# SenseBox-Shield_v12.net
KiCad netlist of a schematic drawn in EAGLE
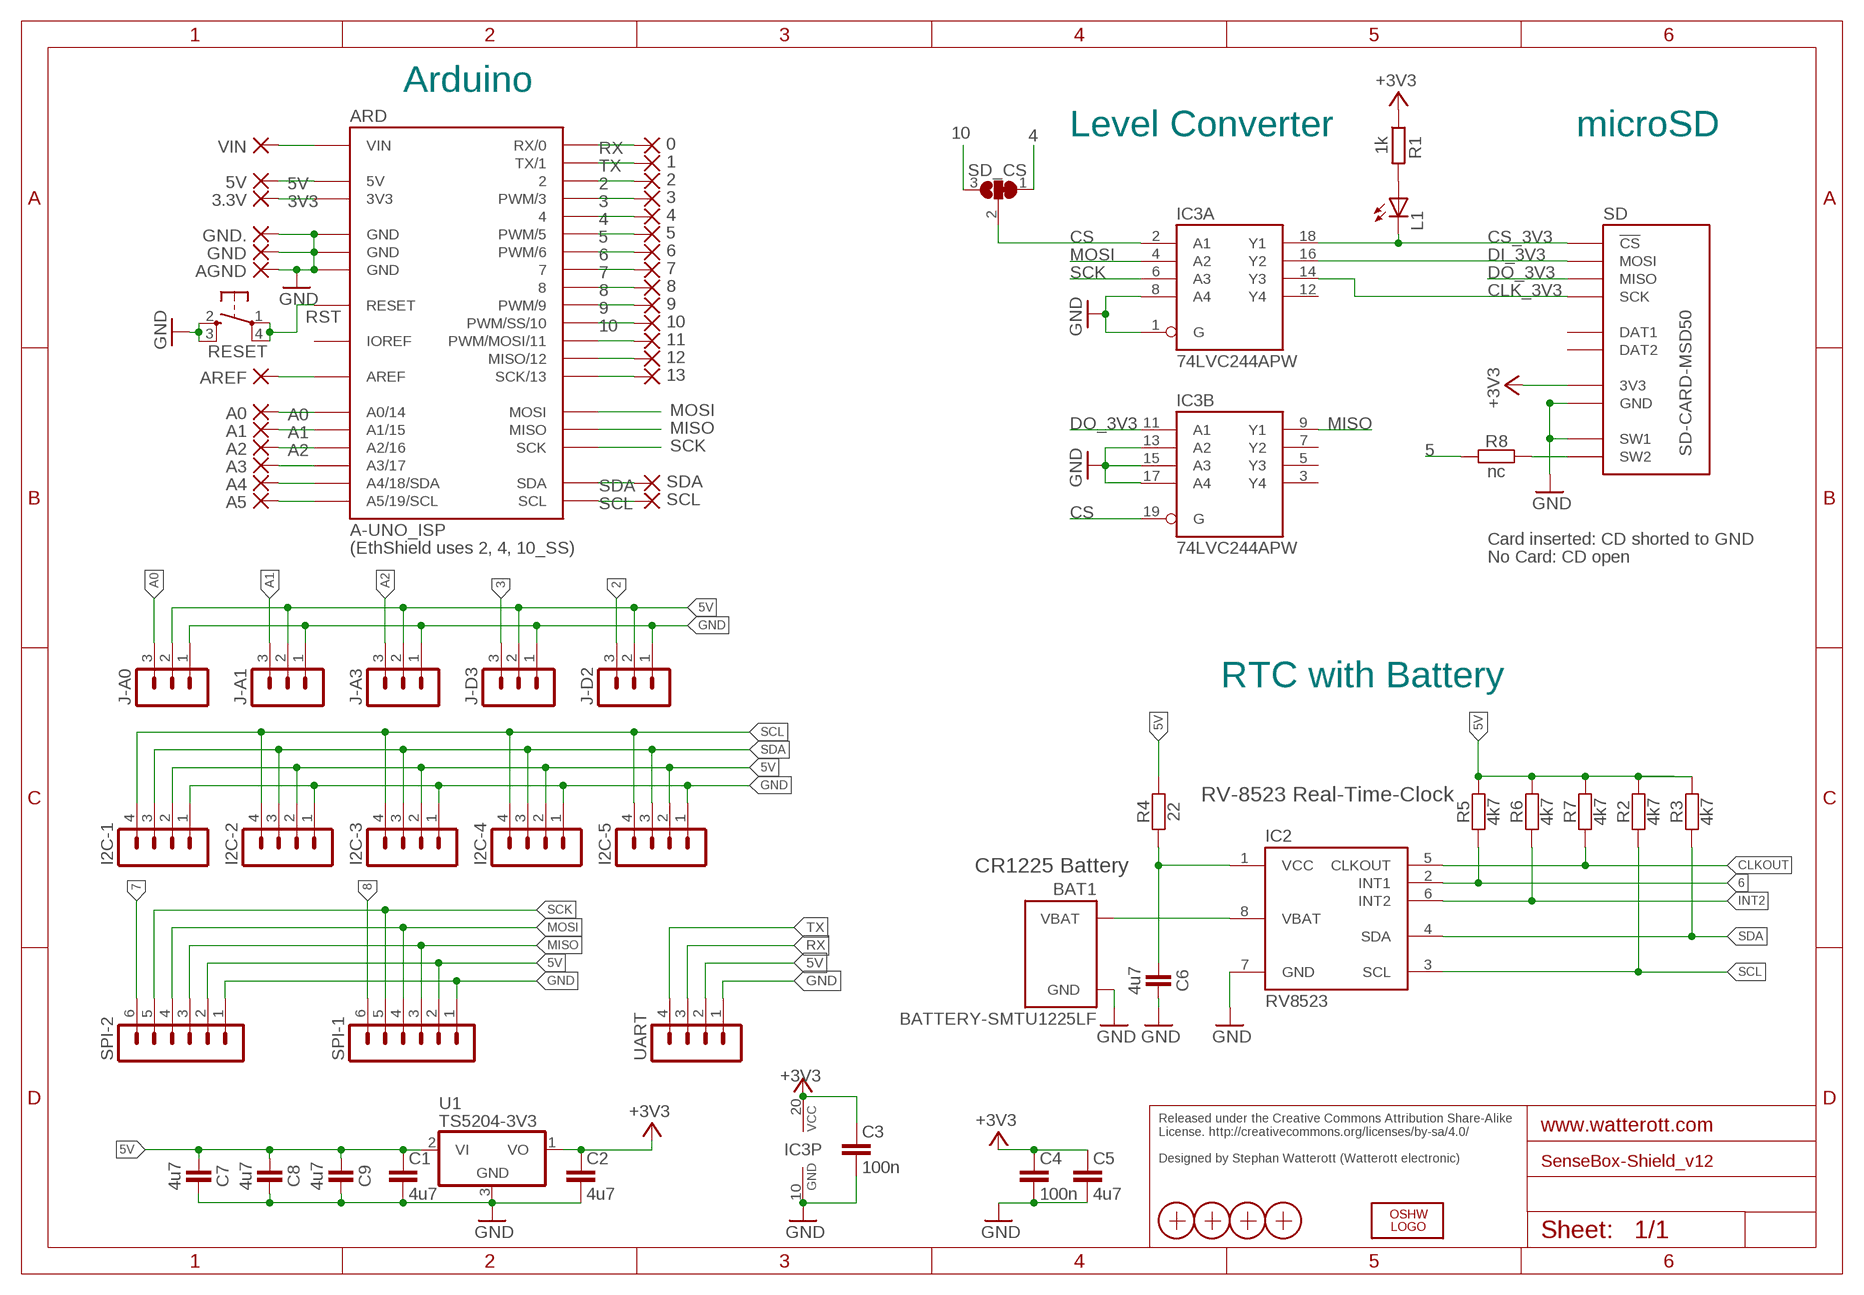
[diagram p0: schematic, sheet 1]

(export (version "E")
  (design (tool "Eeschema 10.0.6"))
  (components
    (comp (ref "0")
      (value "1,6/0,8")
      (footprint "eagle-import:1,6_0,8")
      (libsource (lib "eagle-import") (part "1,6/0,8"))
    )
    (comp (ref "1")
      (value "1,6/0,8")
      (footprint "eagle-import:1,6_0,8")
      (libsource (lib "eagle-import") (part "1,6/0,8"))
    )
    (comp (ref "2")
      (value "1,6/0,8")
      (footprint "eagle-import:1,6_0,8")
      (libsource (lib "eagle-import") (part "1,6/0,8"))
    )
    (comp (ref "3")
      (value "1,6/0,8")
      (footprint "eagle-import:1,6_0,8")
      (libsource (lib "eagle-import") (part "1,6/0,8"))
    )
    (comp (ref "3.3V")
      (value "1,6/0,8")
      (footprint "eagle-import:1,6_0,8")
      (libsource (lib "eagle-import") (part "1,6/0,8"))
    )
    (comp (ref "4")
      (value "1,6/0,8")
      (footprint "eagle-import:1,6_0,8")
      (libsource (lib "eagle-import") (part "1,6/0,8"))
    )
    (comp (ref "5")
      (value "1,6/0,8")
      (footprint "eagle-import:1,6_0,8")
      (libsource (lib "eagle-import") (part "1,6/0,8"))
    )
    (comp (ref "5V")
      (value "1,6/0,8")
      (footprint "eagle-import:1,6_0,8")
      (libsource (lib "eagle-import") (part "1,6/0,8"))
    )
    (comp (ref "6")
      (value "1,6/0,8")
      (footprint "eagle-import:1,6_0,8")
      (libsource (lib "eagle-import") (part "1,6/0,8"))
    )
    (comp (ref "7")
      (value "1,6/0,8")
      (footprint "eagle-import:1,6_0,8")
      (libsource (lib "eagle-import") (part "1,6/0,8"))
    )
    (comp (ref "8")
      (value "1,6/0,8")
      (footprint "eagle-import:1,6_0,8")
      (libsource (lib "eagle-import") (part "1,6/0,8"))
    )
    (comp (ref "9")
      (value "1,6/0,8")
      (footprint "eagle-import:1,6_0,8")
      (libsource (lib "eagle-import") (part "1,6/0,8"))
    )
    (comp (ref "10")
      (value "1,6/0,8")
      (footprint "eagle-import:1,6_0,8")
      (libsource (lib "eagle-import") (part "1,6/0,8"))
    )
    (comp (ref "11")
      (value "1,6/0,8")
      (footprint "eagle-import:1,6_0,8")
      (libsource (lib "eagle-import") (part "1,6/0,8"))
    )
    (comp (ref "12")
      (value "1,6/0,8")
      (footprint "eagle-import:1,6_0,8")
      (libsource (lib "eagle-import") (part "1,6/0,8"))
    )
    (comp (ref "13")
      (value "1,6/0,8")
      (footprint "eagle-import:1,6_0,8")
      (libsource (lib "eagle-import") (part "1,6/0,8"))
    )
    (comp (ref "A0")
      (value "1,6/0,8")
      (footprint "eagle-import:1,6_0,8")
      (libsource (lib "eagle-import") (part "1,6/0,8"))
    )
    (comp (ref "A1")
      (value "1,6/0,8")
      (footprint "eagle-import:1,6_0,8")
      (libsource (lib "eagle-import") (part "1,6/0,8"))
    )
    (comp (ref "A2")
      (value "1,6/0,8")
      (footprint "eagle-import:1,6_0,8")
      (libsource (lib "eagle-import") (part "1,6/0,8"))
    )
    (comp (ref "A3")
      (value "1,6/0,8")
      (footprint "eagle-import:1,6_0,8")
      (libsource (lib "eagle-import") (part "1,6/0,8"))
    )
    (comp (ref "A4")
      (value "1,6/0,8")
      (footprint "eagle-import:1,6_0,8")
      (libsource (lib "eagle-import") (part "1,6/0,8"))
    )
    (comp (ref "A5")
      (value "1,6/0,8")
      (footprint "eagle-import:1,6_0,8")
      (libsource (lib "eagle-import") (part "1,6/0,8"))
    )
    (comp (ref "AGND")
      (value "1,6/0,8")
      (footprint "eagle-import:1,6_0,8")
      (libsource (lib "eagle-import") (part "1,6/0,8"))
    )
    (comp (ref "ARD")
      (value "A-UNO_ISP")
      (footprint "eagle-import:A-UNO-ISP")
      (libsource (lib "eagle-import") (part "A-UNO_ISP"))
    )
    (comp (ref "AREF")
      (value "1,6/0,8")
      (footprint "eagle-import:1,6_0,8")
      (libsource (lib "eagle-import") (part "1,6/0,8"))
    )
    (comp (ref "BAT1")
      (value "BATTERY-SMTU1225LF")
      (footprint "eagle-import:BAT-SMTU1225LF")
      (libsource (lib "eagle-import") (part "BATTERY-SMTU1225LF"))
    )
    (comp (ref "C1")
      (value "4u7")
      (footprint "eagle-import:C0402K")
      (libsource (lib "eagle-import") (part "C-EUC0402K"))
    )
    (comp (ref "C2")
      (value "4u7")
      (footprint "eagle-import:C0402K")
      (libsource (lib "eagle-import") (part "C-EUC0402K"))
    )
    (comp (ref "C3")
      (value "100n")
      (footprint "eagle-import:C0402K")
      (libsource (lib "eagle-import") (part "C-EUC0402K"))
    )
    (comp (ref "C4")
      (value "100n")
      (footprint "eagle-import:C0402K")
      (libsource (lib "eagle-import") (part "C-EUC0402K"))
    )
    (comp (ref "C5")
      (value "4u7")
      (footprint "eagle-import:C0402K")
      (libsource (lib "eagle-import") (part "C-EUC0402K"))
    )
    (comp (ref "C6")
      (value "4u7")
      (footprint "eagle-import:C0402")
      (libsource (lib "eagle-import") (part "CAPACITOR-0402"))
    )
    (comp (ref "C7")
      (value "4u7")
      (footprint "eagle-import:C0402")
      (libsource (lib "eagle-import") (part "CAPACITOR-0402"))
    )
    (comp (ref "C8")
      (value "4u7")
      (footprint "eagle-import:C0402")
      (libsource (lib "eagle-import") (part "CAPACITOR-0402"))
    )
    (comp (ref "C9")
      (value "4u7")
      (footprint "eagle-import:C0402")
      (libsource (lib "eagle-import") (part "CAPACITOR-0402"))
    )
    (comp (ref "GND")
      (value "1,6/0,8")
      (footprint "eagle-import:1,6_0,8")
      (libsource (lib "eagle-import") (part "1,6/0,8"))
    )
    (comp (ref "GND.")
      (value "1,6/0,8")
      (footprint "eagle-import:1,6_0,8")
      (libsource (lib "eagle-import") (part "1,6/0,8"))
    )
    (comp (ref "I2C-1")
      (value "JST_PH_4B4B-PH-SM4-TB")
      (footprint "eagle-import:JST_B4B-PH-SM4-TB")
      (libsource (lib "eagle-import") (part "JST_PH_4B4B-PH-SM4-TB"))
    )
    (comp (ref "I2C-2")
      (value "JST_PH_4B4B-PH-SM4-TB")
      (footprint "eagle-import:JST_B4B-PH-SM4-TB")
      (libsource (lib "eagle-import") (part "JST_PH_4B4B-PH-SM4-TB"))
    )
    (comp (ref "I2C-3")
      (value "JST_PH_4B4B-PH-SM4-TB")
      (footprint "eagle-import:JST_B4B-PH-SM4-TB")
      (libsource (lib "eagle-import") (part "JST_PH_4B4B-PH-SM4-TB"))
    )
    (comp (ref "I2C-4")
      (value "JST_PH_4B4B-PH-SM4-TB")
      (footprint "eagle-import:JST_B4B-PH-SM4-TB")
      (libsource (lib "eagle-import") (part "JST_PH_4B4B-PH-SM4-TB"))
    )
    (comp (ref "I2C-5")
      (value "JST_PH_4B4B-PH-SM4-TB")
      (footprint "eagle-import:JST_B4B-PH-SM4-TB")
      (libsource (lib "eagle-import") (part "JST_PH_4B4B-PH-SM4-TB"))
    )
    (comp (ref "IC2")
      (value "RV8523")
      (footprint "eagle-import:RTC-C3")
      (libsource (lib "eagle-import") (part "RV8523-C3"))
    )
    (comp (ref "IC3")
      (value "74LVC244APW")
      (footprint "eagle-import:TSSOP20")
      (libsource (lib "eagle-import") (part "74244PWLVC"))
    )
    (comp (ref "J-A0")
      (value "JST_PH_3B3B-PH-SM4-TB")
      (footprint "eagle-import:JST_B3B-PH-SM4-TB")
      (libsource (lib "eagle-import") (part "JST_PH_3B3B-PH-SM4-TB"))
    )
    (comp (ref "J-A1")
      (value "JST_PH_3B3B-PH-SM4-TB")
      (footprint "eagle-import:JST_B3B-PH-SM4-TB")
      (libsource (lib "eagle-import") (part "JST_PH_3B3B-PH-SM4-TB"))
    )
    (comp (ref "J-A3")
      (value "JST_PH_3B3B-PH-SM4-TB")
      (footprint "eagle-import:JST_B3B-PH-SM4-TB")
      (libsource (lib "eagle-import") (part "JST_PH_3B3B-PH-SM4-TB"))
    )
    (comp (ref "J-D2")
      (value "JST_PH_3B3B-PH-SM4-TB")
      (footprint "eagle-import:JST_B3B-PH-SM4-TB")
      (libsource (lib "eagle-import") (part "JST_PH_3B3B-PH-SM4-TB"))
    )
    (comp (ref "J-D3")
      (value "JST_PH_3B3B-PH-SM4-TB")
      (footprint "eagle-import:JST_B3B-PH-SM4-TB")
      (libsource (lib "eagle-import") (part "JST_PH_3B3B-PH-SM4-TB"))
    )
    (comp (ref "L1")
      (value "LED-0603")
      (footprint "eagle-import:C0603")
      (libsource (lib "eagle-import") (part "LED-0603"))
    )
    (comp (ref "LOGO3")
      (value "OSHW_LOGO_6MILX0100-NT")
      (footprint "eagle-import:OSHW_6X100_NOTEXT")
      (libsource (lib "eagle-import") (part "OSHW_LOGO_6MILX0100-NT"))
    )
    (comp (ref "R1")
      (value "1k")
      (footprint "eagle-import:R0402")
      (libsource (lib "eagle-import") (part "R-EU_R0402"))
    )
    (comp (ref "R2")
      (value "4k7")
      (footprint "eagle-import:C0402")
      (libsource (lib "eagle-import") (part "RESISTOR-0402"))
    )
    (comp (ref "R3")
      (value "4k7")
      (footprint "eagle-import:C0402")
      (libsource (lib "eagle-import") (part "RESISTOR-0402"))
    )
    (comp (ref "R4")
      (value "22")
      (footprint "eagle-import:C0402")
      (libsource (lib "eagle-import") (part "RESISTOR-0402"))
    )
    (comp (ref "R5")
      (value "4k7")
      (footprint "eagle-import:C0402")
      (libsource (lib "eagle-import") (part "RESISTOR-0402"))
    )
    (comp (ref "R6")
      (value "4k7")
      (footprint "eagle-import:C0402")
      (libsource (lib "eagle-import") (part "RESISTOR-0402"))
    )
    (comp (ref "R7")
      (value "4k7")
      (footprint "eagle-import:C0402")
      (libsource (lib "eagle-import") (part "RESISTOR-0402"))
    )
    (comp (ref "R8")
      (value "nc")
      (footprint "eagle-import:C0402")
      (libsource (lib "eagle-import") (part "RESISTOR-0402"))
    )
    (comp (ref "RESET")
      (value "SW4S")
      (footprint "eagle-import:SW_SMD4")
      (libsource (lib "eagle-import") (part "SW4S"))
    )
    (comp (ref "SCL")
      (value "1,6/0,8")
      (footprint "eagle-import:1,6_0,8")
      (libsource (lib "eagle-import") (part "1,6/0,8"))
    )
    (comp (ref "SD")
      (value "SD-CARD-MSD50")
      (footprint "eagle-import:SD_5031821853")
      (libsource (lib "eagle-import") (part "SD-CARD-MSD50"))
    )
    (comp (ref "SDA")
      (value "1,6/0,8")
      (footprint "eagle-import:1,6_0,8")
      (libsource (lib "eagle-import") (part "1,6/0,8"))
    )
    (comp (ref "SD_CS")
      (value "SJ2W")
      (footprint "eagle-import:SJ_2")
      (libsource (lib "eagle-import") (part "SJ2W"))
    )
    (comp (ref "SPI-1")
      (value "JST_PH_6B6B-PH-SM4-TB")
      (footprint "eagle-import:JST_B6B-PH-SM4-TB")
      (libsource (lib "eagle-import") (part "JST_PH_6B6B-PH-SM4-TB"))
    )
    (comp (ref "SPI-2")
      (value "JST_PH_6B6B-PH-SM4-TB")
      (footprint "eagle-import:JST_B6B-PH-SM4-TB")
      (libsource (lib "eagle-import") (part "JST_PH_6B6B-PH-SM4-TB"))
    )
    (comp (ref "U1")
      (value "TS5204-3V3")
      (footprint "eagle-import:SOT23")
      (libsource (lib "eagle-import") (part "TS5204"))
    )
    (comp (ref "UART")
      (value "JST_PH_4B4B-PH-SM4-TB")
      (footprint "eagle-import:JST_B4B-PH-SM4-TB")
      (libsource (lib "eagle-import") (part "JST_PH_4B4B-PH-SM4-TB"))
    )
    (comp (ref "VIN")
      (value "1,6/0,8")
      (footprint "eagle-import:1,6_0,8")
      (libsource (lib "eagle-import") (part "1,6/0,8"))
    )
    (comp (ref "X1")
      (value "PASSER")
      (footprint "eagle-import:PASSER")
      (libsource (lib "eagle-import") (part "PASSER"))
    )
    (comp (ref "X2")
      (value "PASSER")
      (footprint "eagle-import:PASSER")
      (libsource (lib "eagle-import") (part "PASSER"))
    )
    (comp (ref "X3")
      (value "PASSER")
      (footprint "eagle-import:PASSER")
      (libsource (lib "eagle-import") (part "PASSER"))
    )
    (comp (ref "X4")
      (value "PASSER")
      (footprint "eagle-import:PASSER")
      (libsource (lib "eagle-import") (part "PASSER"))
    )
  )
  (nets
    (net (code "1") (name "+3V3") (class "Default")
      (node (ref "C2") (pin "1") (pinfunction "1_1") (pintype "passive"))
      (node (ref "C3") (pin "1") (pinfunction "1_1") (pintype "passive"))
      (node (ref "C4") (pin "1") (pinfunction "1_1") (pintype "passive"))
      (node (ref "C5") (pin "1") (pinfunction "1_1") (pintype "passive"))
      (node (ref "IC3") (pin "20") (pinfunction "VCC_20") (pintype "power_in"))
      (node (ref "R1") (pin "1") (pinfunction "1_1") (pintype "passive"))
      (node (ref "SD") (pin "VCC") (pinfunction "3V3_VCC") (pintype "bidirectional"))
      (node (ref "U1") (pin "1") (pinfunction "VO_1") (pintype "passive"))
    )
    (net (code "2") (name "/3V3") (class "Default")
      (node (ref "3.3V") (pin "1") (pinfunction "P_1") (pintype "passive"))
      (node (ref "ARD") (pin "3V3") (pinfunction "3V3_3V3") (pintype "power_in"))
    )
    (net (code "3") (name "/4") (class "Default")
      (node (ref "4") (pin "1") (pinfunction "P_1") (pintype "passive"))
      (node (ref "ARD") (pin "4") (pinfunction "4_4") (pintype "bidirectional"))
      (node (ref "SD_CS") (pin "1") (pinfunction "1_1") (pintype "passive"))
    )
    (net (code "4") (name "/5") (class "Default")
      (node (ref "5") (pin "1") (pinfunction "P_1") (pintype "passive"))
      (node (ref "ARD") (pin "5") (pinfunction "PWM/5_5") (pintype "bidirectional"))
      (node (ref "R8") (pin "1") (pinfunction "1_1") (pintype "passive"))
    )
    (net (code "5") (name "/9") (class "Default")
      (node (ref "9") (pin "1") (pinfunction "P_1") (pintype "passive"))
      (node (ref "ARD") (pin "9") (pinfunction "PWM/9_9") (pintype "bidirectional"))
    )
    (net (code "6") (name "/10") (class "Default")
      (node (ref "10") (pin "1") (pinfunction "P_1") (pintype "passive"))
      (node (ref "ARD") (pin "10") (pinfunction "PWM/SS/10_10") (pintype "bidirectional"))
      (node (ref "SD_CS") (pin "3") (pinfunction "3_3") (pintype "passive"))
    )
    (net (code "7") (name "/CLK_3V3") (class "Default")
      (node (ref "IC3") (pin "14") (pinfunction "Y3_14") (pintype "tri_state"))
      (node (ref "SD") (pin "SCK") (pinfunction "SCK_SCK") (pintype "bidirectional"))
    )
    (net (code "8") (name "/CS") (class "Default")
      (node (ref "IC3") (pin "19") (pinfunction "G_19") (pintype "input"))
      (node (ref "IC3") (pin "2") (pinfunction "A1_2") (pintype "input"))
      (node (ref "SD_CS") (pin "2") (pinfunction "2_2") (pintype "passive"))
    )
    (net (code "9") (name "/CS_3V3") (class "Default")
      (node (ref "IC3") (pin "18") (pinfunction "Y1_18") (pintype "tri_state"))
      (node (ref "L1") (pin "C") (pinfunction "C_C") (pintype "passive"))
      (node (ref "SD") (pin "CS") (pinfunction "~{CS}_CS") (pintype "bidirectional"))
    )
    (net (code "10") (name "/DI_3V3") (class "Default")
      (node (ref "IC3") (pin "16") (pinfunction "Y2_16") (pintype "tri_state"))
      (node (ref "SD") (pin "MOSI") (pinfunction "MOSI_MOSI") (pintype "bidirectional"))
    )
    (net (code "11") (name "/DO_3V3") (class "Default")
      (node (ref "IC3") (pin "11") (pinfunction "A1_11") (pintype "input"))
      (node (ref "SD") (pin "MISO") (pinfunction "MISO_MISO") (pintype "bidirectional"))
    )
    (net (code "12") (name "/IOREF") (class "Default")
      (node (ref "ARD") (pin "IOREF") (pinfunction "IOREF_IOREF") (pintype "power_in"))
    )
    (net (code "13") (name "/RST") (class "Default")
      (node (ref "ARD") (pin "RST@1") (pinfunction "RESET_RST@1") (pintype "bidirectional"))
      (node (ref "RESET") (pin "1") (pinfunction "P_1") (pintype "passive"))
      (node (ref "RESET") (pin "4") (pinfunction "P1_4") (pintype "passive"))
    )
    (net (code "14") (name "2") (class "Default")
      (node (ref "2") (pin "1") (pinfunction "P_1") (pintype "passive"))
      (node (ref "ARD") (pin "2") (pinfunction "2_2") (pintype "bidirectional"))
      (node (ref "J-D2") (pin "3") (pinfunction "3_3") (pintype "passive"))
    )
    (net (code "15") (name "3") (class "Default")
      (node (ref "3") (pin "1") (pinfunction "P_1") (pintype "passive"))
      (node (ref "ARD") (pin "3") (pinfunction "PWM/3_3") (pintype "bidirectional"))
      (node (ref "J-D3") (pin "3") (pinfunction "3_3") (pintype "passive"))
    )
    (net (code "16") (name "5V") (class "Default")
      (node (ref "5V") (pin "1") (pinfunction "P_1") (pintype "passive"))
      (node (ref "ARD") (pin "5V") (pinfunction "5V_5V") (pintype "power_in"))
      (node (ref "C1") (pin "1") (pinfunction "1_1") (pintype "passive"))
      (node (ref "C7") (pin "1") (pinfunction "1_1") (pintype "passive"))
      (node (ref "C8") (pin "1") (pinfunction "1_1") (pintype "passive"))
      (node (ref "C9") (pin "1") (pinfunction "1_1") (pintype "passive"))
      (node (ref "I2C-1") (pin "2") (pinfunction "2_2") (pintype "passive"))
      (node (ref "I2C-2") (pin "2") (pinfunction "2_2") (pintype "passive"))
      (node (ref "I2C-3") (pin "2") (pinfunction "2_2") (pintype "passive"))
      (node (ref "I2C-4") (pin "2") (pinfunction "2_2") (pintype "passive"))
      (node (ref "I2C-5") (pin "2") (pinfunction "2_2") (pintype "passive"))
      (node (ref "J-A0") (pin "2") (pinfunction "2_2") (pintype "passive"))
      (node (ref "J-A1") (pin "2") (pinfunction "2_2") (pintype "passive"))
      (node (ref "J-A3") (pin "2") (pinfunction "2_2") (pintype "passive"))
      (node (ref "J-D2") (pin "2") (pinfunction "2_2") (pintype "passive"))
      (node (ref "J-D3") (pin "2") (pinfunction "2_2") (pintype "passive"))
      (node (ref "R2") (pin "2") (pinfunction "2_2") (pintype "passive"))
      (node (ref "R3") (pin "2") (pinfunction "2_2") (pintype "passive"))
      (node (ref "R4") (pin "2") (pinfunction "2_2") (pintype "passive"))
      (node (ref "R5") (pin "2") (pinfunction "2_2") (pintype "passive"))
      (node (ref "R6") (pin "2") (pinfunction "2_2") (pintype "passive"))
      (node (ref "R7") (pin "2") (pinfunction "2_2") (pintype "passive"))
      (node (ref "SPI-1") (pin "2") (pinfunction "2_2") (pintype "passive"))
      (node (ref "SPI-2") (pin "2") (pinfunction "2_2") (pintype "passive"))
      (node (ref "U1") (pin "2") (pinfunction "VI_2") (pintype "input"))
      (node (ref "UART") (pin "2") (pinfunction "2_2") (pintype "passive"))
    )
    (net (code "17") (name "6") (class "Default")
      (node (ref "6") (pin "1") (pinfunction "P_1") (pintype "passive"))
      (node (ref "ARD") (pin "6") (pinfunction "PWM/6_6") (pintype "bidirectional"))
      (node (ref "IC2") (pin "2") (pinfunction "INT1_2") (pintype "bidirectional"))
      (node (ref "R5") (pin "1") (pinfunction "1_1") (pintype "passive"))
    )
    (net (code "18") (name "7") (class "Default")
      (node (ref "7") (pin "1") (pinfunction "P_1") (pintype "passive"))
      (node (ref "ARD") (pin "7") (pinfunction "7_7") (pintype "bidirectional"))
      (node (ref "SPI-2") (pin "6") (pinfunction "6_6") (pintype "passive"))
    )
    (net (code "19") (name "8") (class "Default")
      (node (ref "8") (pin "1") (pinfunction "P_1") (pintype "passive"))
      (node (ref "ARD") (pin "8") (pinfunction "8_8") (pintype "bidirectional"))
      (node (ref "SPI-1") (pin "6") (pinfunction "6_6") (pintype "passive"))
    )
    (net (code "20") (name "A0") (class "Default")
      (node (ref "A0") (pin "1") (pinfunction "P_1") (pintype "passive"))
      (node (ref "ARD") (pin "A0") (pinfunction "A0/14_A0") (pintype "bidirectional"))
      (node (ref "J-A0") (pin "3") (pinfunction "3_3") (pintype "passive"))
    )
    (net (code "21") (name "A1") (class "Default")
      (node (ref "A1") (pin "1") (pinfunction "P_1") (pintype "passive"))
      (node (ref "ARD") (pin "A1") (pinfunction "A1/15_A1") (pintype "bidirectional"))
      (node (ref "J-A1") (pin "3") (pinfunction "3_3") (pintype "passive"))
    )
    (net (code "22") (name "A2") (class "Default")
      (node (ref "A2") (pin "1") (pinfunction "P_1") (pintype "passive"))
      (node (ref "ARD") (pin "A2") (pinfunction "A2/16_A2") (pintype "bidirectional"))
      (node (ref "J-A3") (pin "3") (pinfunction "3_3") (pintype "passive"))
    )
    (net (code "23") (name "CLKOUT") (class "Default")
      (node (ref "IC2") (pin "5") (pinfunction "CLKOUT_5") (pintype "bidirectional"))
      (node (ref "R7") (pin "1") (pinfunction "1_1") (pintype "passive"))
    )
    (net (code "24") (name "GND") (class "Default")
      (node (ref "AGND") (pin "1") (pinfunction "P_1") (pintype "passive"))
      (node (ref "ARD") (pin "GND@1") (pinfunction "GND_GND@1") (pintype "power_in"))
      (node (ref "ARD") (pin "GND@2") (pinfunction "GND_GND@2") (pintype "power_in"))
      (node (ref "ARD") (pin "GND@3") (pinfunction "GND_GND@3") (pintype "power_in"))
      (node (ref "BAT1") (pin "-") (pinfunction "GND_-") (pintype "power_in"))
      (node (ref "C1") (pin "2") (pinfunction "2_2") (pintype "passive"))
      (node (ref "C2") (pin "2") (pinfunction "2_2") (pintype "passive"))
      (node (ref "C3") (pin "2") (pinfunction "2_2") (pintype "passive"))
      (node (ref "C4") (pin "2") (pinfunction "2_2") (pintype "passive"))
      (node (ref "C5") (pin "2") (pinfunction "2_2") (pintype "passive"))
      (node (ref "C6") (pin "2") (pinfunction "2_2") (pintype "passive"))
      (node (ref "C7") (pin "2") (pinfunction "2_2") (pintype "passive"))
      (node (ref "C8") (pin "2") (pinfunction "2_2") (pintype "passive"))
      (node (ref "C9") (pin "2") (pinfunction "2_2") (pintype "passive"))
      (node (ref "GND") (pin "1") (pinfunction "P_1") (pintype "passive"))
      (node (ref "GND.") (pin "1") (pinfunction "P_1") (pintype "passive"))
      (node (ref "I2C-1") (pin "1") (pinfunction "1_1") (pintype "passive"))
      (node (ref "I2C-2") (pin "1") (pinfunction "1_1") (pintype "passive"))
      (node (ref "I2C-3") (pin "1") (pinfunction "1_1") (pintype "passive"))
      (node (ref "I2C-4") (pin "1") (pinfunction "1_1") (pintype "passive"))
      (node (ref "I2C-5") (pin "1") (pinfunction "1_1") (pintype "passive"))
      (node (ref "IC2") (pin "7") (pinfunction "GND_7") (pintype "power_in"))
      (node (ref "IC3") (pin "1") (pinfunction "G_1") (pintype "input"))
      (node (ref "IC3") (pin "10") (pinfunction "GND_10") (pintype "power_in"))
      (node (ref "IC3") (pin "13") (pinfunction "A2_13") (pintype "input"))
      (node (ref "IC3") (pin "15") (pinfunction "A3_15") (pintype "input"))
      (node (ref "IC3") (pin "17") (pinfunction "A4_17") (pintype "input"))
      (node (ref "IC3") (pin "8") (pinfunction "A4_8") (pintype "input"))
      (node (ref "J-A0") (pin "1") (pinfunction "1_1") (pintype "passive"))
      (node (ref "J-A1") (pin "1") (pinfunction "1_1") (pintype "passive"))
      (node (ref "J-A3") (pin "1") (pinfunction "1_1") (pintype "passive"))
      (node (ref "J-D2") (pin "1") (pinfunction "1_1") (pintype "passive"))
      (node (ref "J-D3") (pin "1") (pinfunction "1_1") (pintype "passive"))
      (node (ref "RESET") (pin "2") (pinfunction "S_2") (pintype "passive"))
      (node (ref "RESET") (pin "3") (pinfunction "S1_3") (pintype "passive"))
      (node (ref "SD") (pin "GND") (pinfunction "GND_GND") (pintype "bidirectional"))
      (node (ref "SD") (pin "SW1") (pinfunction "SW1_SW1") (pintype "bidirectional"))
      (node (ref "SPI-1") (pin "1") (pinfunction "1_1") (pintype "passive"))
      (node (ref "SPI-2") (pin "1") (pinfunction "1_1") (pintype "passive"))
      (node (ref "U1") (pin "3") (pinfunction "GND_3") (pintype "passive"))
      (node (ref "UART") (pin "1") (pinfunction "1_1") (pintype "passive"))
    )
    (net (code "25") (name "INT2") (class "Default")
      (node (ref "IC2") (pin "6") (pinfunction "INT2_6") (pintype "bidirectional"))
      (node (ref "R6") (pin "1") (pinfunction "1_1") (pintype "passive"))
    )
    (net (code "26") (name "MISO") (class "Default")
      (node (ref "ARD") (pin "MISO") (pinfunction "MISO_MISO") (pintype "bidirectional"))
      (node (ref "IC3") (pin "9") (pinfunction "Y1_9") (pintype "tri_state"))
      (node (ref "SPI-1") (pin "3") (pinfunction "3_3") (pintype "passive"))
      (node (ref "SPI-2") (pin "3") (pinfunction "3_3") (pintype "passive"))
    )
    (net (code "27") (name "MOSI") (class "Default")
      (node (ref "ARD") (pin "MOSI") (pinfunction "MOSI_MOSI") (pintype "bidirectional"))
      (node (ref "IC3") (pin "4") (pinfunction "A2_4") (pintype "input"))
      (node (ref "SPI-1") (pin "4") (pinfunction "4_4") (pintype "passive"))
      (node (ref "SPI-2") (pin "4") (pinfunction "4_4") (pintype "passive"))
    )
    (net (code "28") (name "Net-(11-P)") (class "Default")
      (node (ref "11") (pin "1") (pinfunction "P_1") (pintype "passive"))
      (node (ref "ARD") (pin "11") (pinfunction "PWM/MOSI/11_11") (pintype "bidirectional"))
    )
    (net (code "29") (name "Net-(12-P)") (class "Default")
      (node (ref "12") (pin "1") (pinfunction "P_1") (pintype "passive"))
      (node (ref "ARD") (pin "12") (pinfunction "MISO/12_12") (pintype "bidirectional"))
    )
    (net (code "30") (name "Net-(13-P)") (class "Default")
      (node (ref "13") (pin "1") (pinfunction "P_1") (pintype "passive"))
      (node (ref "ARD") (pin "13") (pinfunction "SCK/13_13") (pintype "bidirectional"))
    )
    (net (code "31") (name "Net-(A3-P)") (class "Default")
      (node (ref "A3") (pin "1") (pinfunction "P_1") (pintype "passive"))
      (node (ref "ARD") (pin "A3") (pinfunction "A3/17_A3") (pintype "bidirectional"))
    )
    (net (code "32") (name "Net-(A4-P)") (class "Default")
      (node (ref "A4") (pin "1") (pinfunction "P_1") (pintype "passive"))
      (node (ref "ARD") (pin "A4") (pinfunction "A4/18/SDA_A4") (pintype "bidirectional"))
    )
    (net (code "33") (name "Net-(A5-P)") (class "Default")
      (node (ref "A5") (pin "1") (pinfunction "P_1") (pintype "passive"))
      (node (ref "ARD") (pin "A5") (pinfunction "A5/19/SCL_A5") (pintype "bidirectional"))
    )
    (net (code "34") (name "Net-(AREF-P)") (class "Default")
      (node (ref "ARD") (pin "AREF") (pinfunction "AREF_AREF") (pintype "power_in"))
      (node (ref "AREF") (pin "1") (pinfunction "P_1") (pintype "passive"))
    )
    (net (code "35") (name "Net-(BAT1-VBAT)") (class "Default")
      (node (ref "BAT1") (pin "+") (pinfunction "VBAT_+") (pintype "power_in"))
      (node (ref "IC2") (pin "8") (pinfunction "VBAT_8") (pintype "power_in"))
    )
    (net (code "36") (name "Net-(IC2-VCC)") (class "Default")
      (node (ref "C6") (pin "1") (pinfunction "1_1") (pintype "passive"))
      (node (ref "IC2") (pin "1") (pinfunction "VCC_1") (pintype "power_in"))
      (node (ref "R4") (pin "1") (pinfunction "1_1") (pintype "passive"))
    )
    (net (code "37") (name "Net-(L1-PadA)") (class "Default")
      (node (ref "L1") (pin "A") (pinfunction "A_A") (pintype "passive"))
      (node (ref "R1") (pin "2") (pinfunction "2_2") (pintype "passive"))
    )
    (net (code "38") (name "Net-(R8-Pad2)") (class "Default")
      (node (ref "R8") (pin "2") (pinfunction "2_2") (pintype "passive"))
      (node (ref "SD") (pin "SW2") (pinfunction "SW2_SW2") (pintype "bidirectional"))
    )
    (net (code "39") (name "Net-(VIN-P)") (class "Default")
      (node (ref "ARD") (pin "VIN") (pinfunction "VIN_VIN") (pintype "power_in"))
      (node (ref "VIN") (pin "1") (pinfunction "P_1") (pintype "passive"))
    )
    (net (code "40") (name "RX") (class "Default")
      (node (ref "0") (pin "1") (pinfunction "P_1") (pintype "passive"))
      (node (ref "ARD") (pin "0") (pinfunction "RX/0_0") (pintype "bidirectional"))
      (node (ref "UART") (pin "3") (pinfunction "3_3") (pintype "passive"))
    )
    (net (code "41") (name "SCK") (class "Default")
      (node (ref "ARD") (pin "SCK") (pinfunction "SCK_SCK") (pintype "bidirectional"))
      (node (ref "IC3") (pin "6") (pinfunction "A3_6") (pintype "input"))
      (node (ref "SPI-1") (pin "5") (pinfunction "5_5") (pintype "passive"))
      (node (ref "SPI-2") (pin "5") (pinfunction "5_5") (pintype "passive"))
    )
    (net (code "42") (name "SCL") (class "Default")
      (node (ref "ARD") (pin "SCL") (pinfunction "SCL_SCL") (pintype "bidirectional"))
      (node (ref "I2C-1") (pin "4") (pinfunction "4_4") (pintype "passive"))
      (node (ref "I2C-2") (pin "4") (pinfunction "4_4") (pintype "passive"))
      (node (ref "I2C-3") (pin "4") (pinfunction "4_4") (pintype "passive"))
      (node (ref "I2C-4") (pin "4") (pinfunction "4_4") (pintype "passive"))
      (node (ref "I2C-5") (pin "4") (pinfunction "4_4") (pintype "passive"))
      (node (ref "IC2") (pin "3") (pinfunction "SCL_3") (pintype "bidirectional"))
      (node (ref "R2") (pin "1") (pinfunction "1_1") (pintype "passive"))
      (node (ref "SCL") (pin "1") (pinfunction "P_1") (pintype "passive"))
    )
    (net (code "43") (name "SDA") (class "Default")
      (node (ref "ARD") (pin "SDA") (pinfunction "SDA_SDA") (pintype "bidirectional"))
      (node (ref "I2C-1") (pin "3") (pinfunction "3_3") (pintype "passive"))
      (node (ref "I2C-2") (pin "3") (pinfunction "3_3") (pintype "passive"))
      (node (ref "I2C-3") (pin "3") (pinfunction "3_3") (pintype "passive"))
      (node (ref "I2C-4") (pin "3") (pinfunction "3_3") (pintype "passive"))
      (node (ref "I2C-5") (pin "3") (pinfunction "3_3") (pintype "passive"))
      (node (ref "IC2") (pin "4") (pinfunction "SDA_4") (pintype "bidirectional"))
      (node (ref "R3") (pin "1") (pinfunction "1_1") (pintype "passive"))
      (node (ref "SDA") (pin "1") (pinfunction "P_1") (pintype "passive"))
    )
    (net (code "44") (name "TX") (class "Default")
      (node (ref "1") (pin "1") (pinfunction "P_1") (pintype "passive"))
      (node (ref "ARD") (pin "1") (pinfunction "TX/1_1") (pintype "bidirectional"))
      (node (ref "UART") (pin "4") (pinfunction "4_4") (pintype "passive"))
    )
    (net (code "45") (name "unconnected-(IC3A-Y4-Pad12)") (class "Default")
      (node (ref "IC3") (pin "12") (pinfunction "Y4_12") (pintype "tri_state"))
    )
    (net (code "46") (name "unconnected-(IC3B-Y2-Pad7)") (class "Default")
      (node (ref "IC3") (pin "7") (pinfunction "Y2_7") (pintype "tri_state"))
    )
    (net (code "47") (name "unconnected-(IC3B-Y3-Pad5)") (class "Default")
      (node (ref "IC3") (pin "5") (pinfunction "Y3_5") (pintype "tri_state"))
    )
    (net (code "48") (name "unconnected-(IC3B-Y4-Pad3)") (class "Default")
      (node (ref "IC3") (pin "3") (pinfunction "Y4_3") (pintype "tri_state"))
    )
    (net (code "49") (name "unconnected-(SD-PadDAT1)") (class "Default")
      (node (ref "SD") (pin "DAT1") (pinfunction "DAT1_DAT1") (pintype "bidirectional"))
    )
    (net (code "50") (name "unconnected-(SD-PadDAT2)") (class "Default")
      (node (ref "SD") (pin "DAT2") (pinfunction "DAT2_DAT2") (pintype "bidirectional"))
    )
  )
)
